# OpAmp_NonInvertente.net
KiCad netlist of a schematic drawn in EAGLE
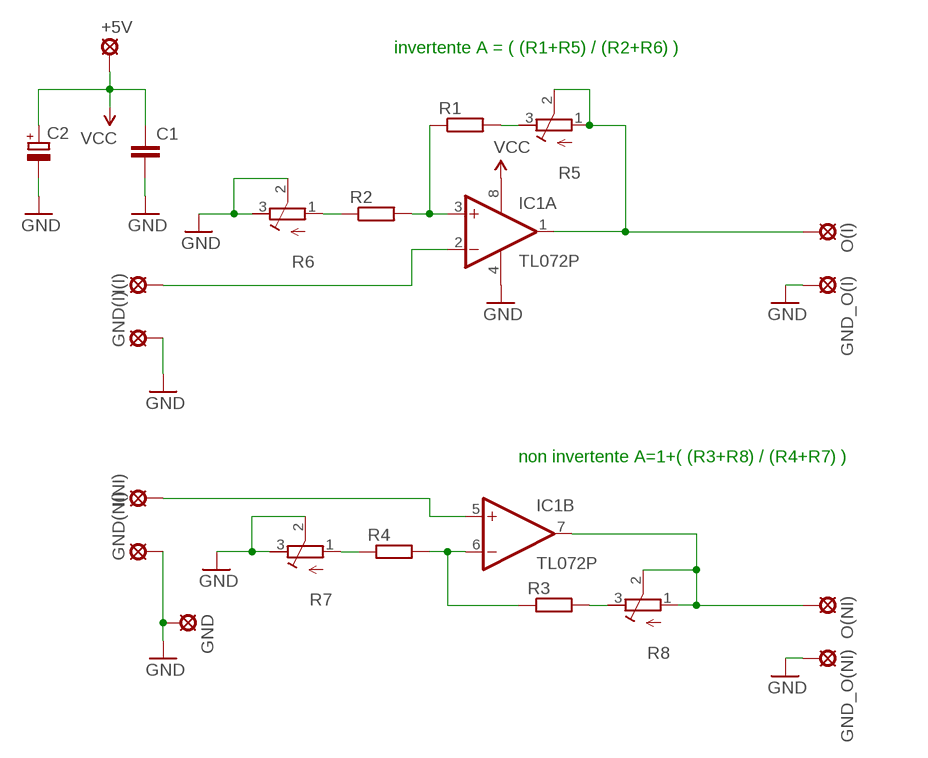
[diagram p0: schematic, sheet 1]

(export (version "E")
  (design (tool "Eeschema 10.0.6"))
  (components
    (comp (ref "+5V")
      (value "LSP10")
      (footprint "eagle-import:LSP10")
      (libsource (lib "eagle-import") (part "LSP10"))
    )
    (comp (ref "C1")
      (value "C-EU025-024X044")
      (footprint "eagle-import:C025-024X044")
      (libsource (lib "eagle-import") (part "C-EU025-024X044"))
    )
    (comp (ref "C2")
      (value "CPOL-EUE2.5-6")
      (footprint "eagle-import:E2,5-6")
      (libsource (lib "eagle-import") (part "CPOL-EUE2.5-6"))
    )
    (comp (ref "GND")
      (value "LSP10")
      (footprint "eagle-import:LSP10")
      (libsource (lib "eagle-import") (part "LSP10"))
    )
    (comp (ref "GND(I)")
      (value "LSP10")
      (footprint "eagle-import:LSP10")
      (libsource (lib "eagle-import") (part "LSP10"))
    )
    (comp (ref "GND(NI)")
      (value "LSP10")
      (footprint "eagle-import:LSP10")
      (libsource (lib "eagle-import") (part "LSP10"))
    )
    (comp (ref "GND_O(I)")
      (value "LSP10")
      (footprint "eagle-import:LSP10")
      (libsource (lib "eagle-import") (part "LSP10"))
    )
    (comp (ref "GND_O(NI)")
      (value "LSP10")
      (footprint "eagle-import:LSP10")
      (libsource (lib "eagle-import") (part "LSP10"))
    )
    (comp (ref "I(I)")
      (value "LSP10")
      (footprint "eagle-import:LSP10")
      (libsource (lib "eagle-import") (part "LSP10"))
    )
    (comp (ref "I(NI)")
      (value "LSP10")
      (footprint "eagle-import:LSP10")
      (libsource (lib "eagle-import") (part "LSP10"))
    )
    (comp (ref "IC1")
      (value "TL072P")
      (footprint "eagle-import:DIL08")
      (libsource (lib "eagle-import") (part "TL072P"))
    )
    (comp (ref "O(I)")
      (value "LSP10")
      (footprint "eagle-import:LSP10")
      (libsource (lib "eagle-import") (part "LSP10"))
    )
    (comp (ref "O(NI)")
      (value "LSP10")
      (footprint "eagle-import:LSP10")
      (libsource (lib "eagle-import") (part "LSP10"))
    )
    (comp (ref "R1")
      (value "R-EU_0309/10")
      (footprint "eagle-import:0309_10")
      (libsource (lib "eagle-import") (part "R-EU_0309/10"))
    )
    (comp (ref "R2")
      (value "R-EU_0309/10")
      (footprint "eagle-import:0309_10")
      (libsource (lib "eagle-import") (part "R-EU_0309/10"))
    )
    (comp (ref "R3")
      (value "R-EU_0309/10")
      (footprint "eagle-import:0309_10")
      (libsource (lib "eagle-import") (part "R-EU_0309/10"))
    )
    (comp (ref "R4")
      (value "R-EU_0309/10")
      (footprint "eagle-import:0309_10")
      (libsource (lib "eagle-import") (part "R-EU_0309/10"))
    )
    (comp (ref "R5")
      (value "R-TRIMM3339P")
      (footprint "eagle-import:RTRIM3339P")
      (libsource (lib "eagle-import") (part "R-TRIMM3339P"))
    )
    (comp (ref "R6")
      (value "R-TRIMM3339P")
      (footprint "eagle-import:RTRIM3339P")
      (libsource (lib "eagle-import") (part "R-TRIMM3339P"))
    )
    (comp (ref "R7")
      (value "R-TRIMM3339P")
      (footprint "eagle-import:RTRIM3339P")
      (libsource (lib "eagle-import") (part "R-TRIMM3339P"))
    )
    (comp (ref "R8")
      (value "R-TRIMM3339P")
      (footprint "eagle-import:RTRIM3339P")
      (libsource (lib "eagle-import") (part "R-TRIMM3339P"))
    )
  )
  (nets
    (net (code "1") (name "GND") (class "Default")
      (node (ref "C1") (pin "2") (pinfunction "2_2") (pintype "passive"))
      (node (ref "C2") (pin "-") (pinfunction "-_-") (pintype "passive"))
      (node (ref "GND") (pin "MP") (pinfunction "MP_MP") (pintype "passive"))
      (node (ref "GND(I)") (pin "MP") (pinfunction "MP_MP") (pintype "passive"))
      (node (ref "GND(NI)") (pin "MP") (pinfunction "MP_MP") (pintype "passive"))
      (node (ref "GND_O(I)") (pin "MP") (pinfunction "MP_MP") (pintype "passive"))
      (node (ref "GND_O(NI)") (pin "MP") (pinfunction "MP_MP") (pintype "passive"))
      (node (ref "IC1") (pin "4") (pinfunction "V-_4") (pintype "power_in"))
      (node (ref "R6") (pin "2") (pinfunction "S_2") (pintype "passive"))
      (node (ref "R6") (pin "3") (pinfunction "E_3") (pintype "passive"))
      (node (ref "R7") (pin "2") (pinfunction "S_2") (pintype "passive"))
      (node (ref "R7") (pin "3") (pinfunction "E_3") (pintype "passive"))
    )
    (net (code "2") (name "Net-(IC1A-+IN)") (class "Default")
      (node (ref "IC1") (pin "3") (pinfunction "+IN_3") (pintype "input"))
      (node (ref "R1") (pin "1") (pinfunction "1_1") (pintype "passive"))
      (node (ref "R2") (pin "2") (pinfunction "2_2") (pintype "passive"))
    )
    (net (code "3") (name "Net-(IC1A--IN)") (class "Default")
      (node (ref "I(I)") (pin "MP") (pinfunction "MP_MP") (pintype "passive"))
      (node (ref "IC1") (pin "2") (pinfunction "-IN_2") (pintype "input"))
    )
    (net (code "4") (name "Net-(IC1A-OUT)") (class "Default")
      (node (ref "IC1") (pin "1") (pinfunction "OUT_1") (pintype "output"))
      (node (ref "O(I)") (pin "MP") (pinfunction "MP_MP") (pintype "passive"))
      (node (ref "R5") (pin "1") (pinfunction "A_1") (pintype "passive"))
      (node (ref "R5") (pin "2") (pinfunction "S_2") (pintype "passive"))
    )
    (net (code "5") (name "Net-(IC1B-+IN)") (class "Default")
      (node (ref "I(NI)") (pin "MP") (pinfunction "MP_MP") (pintype "passive"))
      (node (ref "IC1") (pin "5") (pinfunction "+IN_5") (pintype "input"))
    )
    (net (code "6") (name "Net-(IC1B--IN)") (class "Default")
      (node (ref "IC1") (pin "6") (pinfunction "-IN_6") (pintype "input"))
      (node (ref "R3") (pin "1") (pinfunction "1_1") (pintype "passive"))
      (node (ref "R4") (pin "2") (pinfunction "2_2") (pintype "passive"))
    )
    (net (code "7") (name "Net-(IC1B-OUT)") (class "Default")
      (node (ref "IC1") (pin "7") (pinfunction "OUT_7") (pintype "output"))
      (node (ref "O(NI)") (pin "MP") (pinfunction "MP_MP") (pintype "passive"))
      (node (ref "R8") (pin "1") (pinfunction "A_1") (pintype "passive"))
      (node (ref "R8") (pin "2") (pinfunction "S_2") (pintype "passive"))
    )
    (net (code "8") (name "Net-(R5-E)") (class "Default")
      (node (ref "R1") (pin "2") (pinfunction "2_2") (pintype "passive"))
      (node (ref "R5") (pin "3") (pinfunction "E_3") (pintype "passive"))
    )
    (net (code "9") (name "Net-(R6-A)") (class "Default")
      (node (ref "R2") (pin "1") (pinfunction "1_1") (pintype "passive"))
      (node (ref "R6") (pin "1") (pinfunction "A_1") (pintype "passive"))
    )
    (net (code "10") (name "Net-(R7-A)") (class "Default")
      (node (ref "R4") (pin "1") (pinfunction "1_1") (pintype "passive"))
      (node (ref "R7") (pin "1") (pinfunction "A_1") (pintype "passive"))
    )
    (net (code "11") (name "Net-(R8-E)") (class "Default")
      (node (ref "R3") (pin "2") (pinfunction "2_2") (pintype "passive"))
      (node (ref "R8") (pin "3") (pinfunction "E_3") (pintype "passive"))
    )
    (net (code "12") (name "VCC") (class "Default")
      (node (ref "+5V") (pin "MP") (pinfunction "MP_MP") (pintype "passive"))
      (node (ref "C1") (pin "1") (pinfunction "1_1") (pintype "passive"))
      (node (ref "C2") (pin "+") (pinfunction "+_+") (pintype "passive"))
      (node (ref "IC1") (pin "8") (pinfunction "V+_8") (pintype "power_in"))
    )
  )
)
